# Deneigus_PI_Arduino.net
KiCad netlist of a schematic drawn in Altium Designer
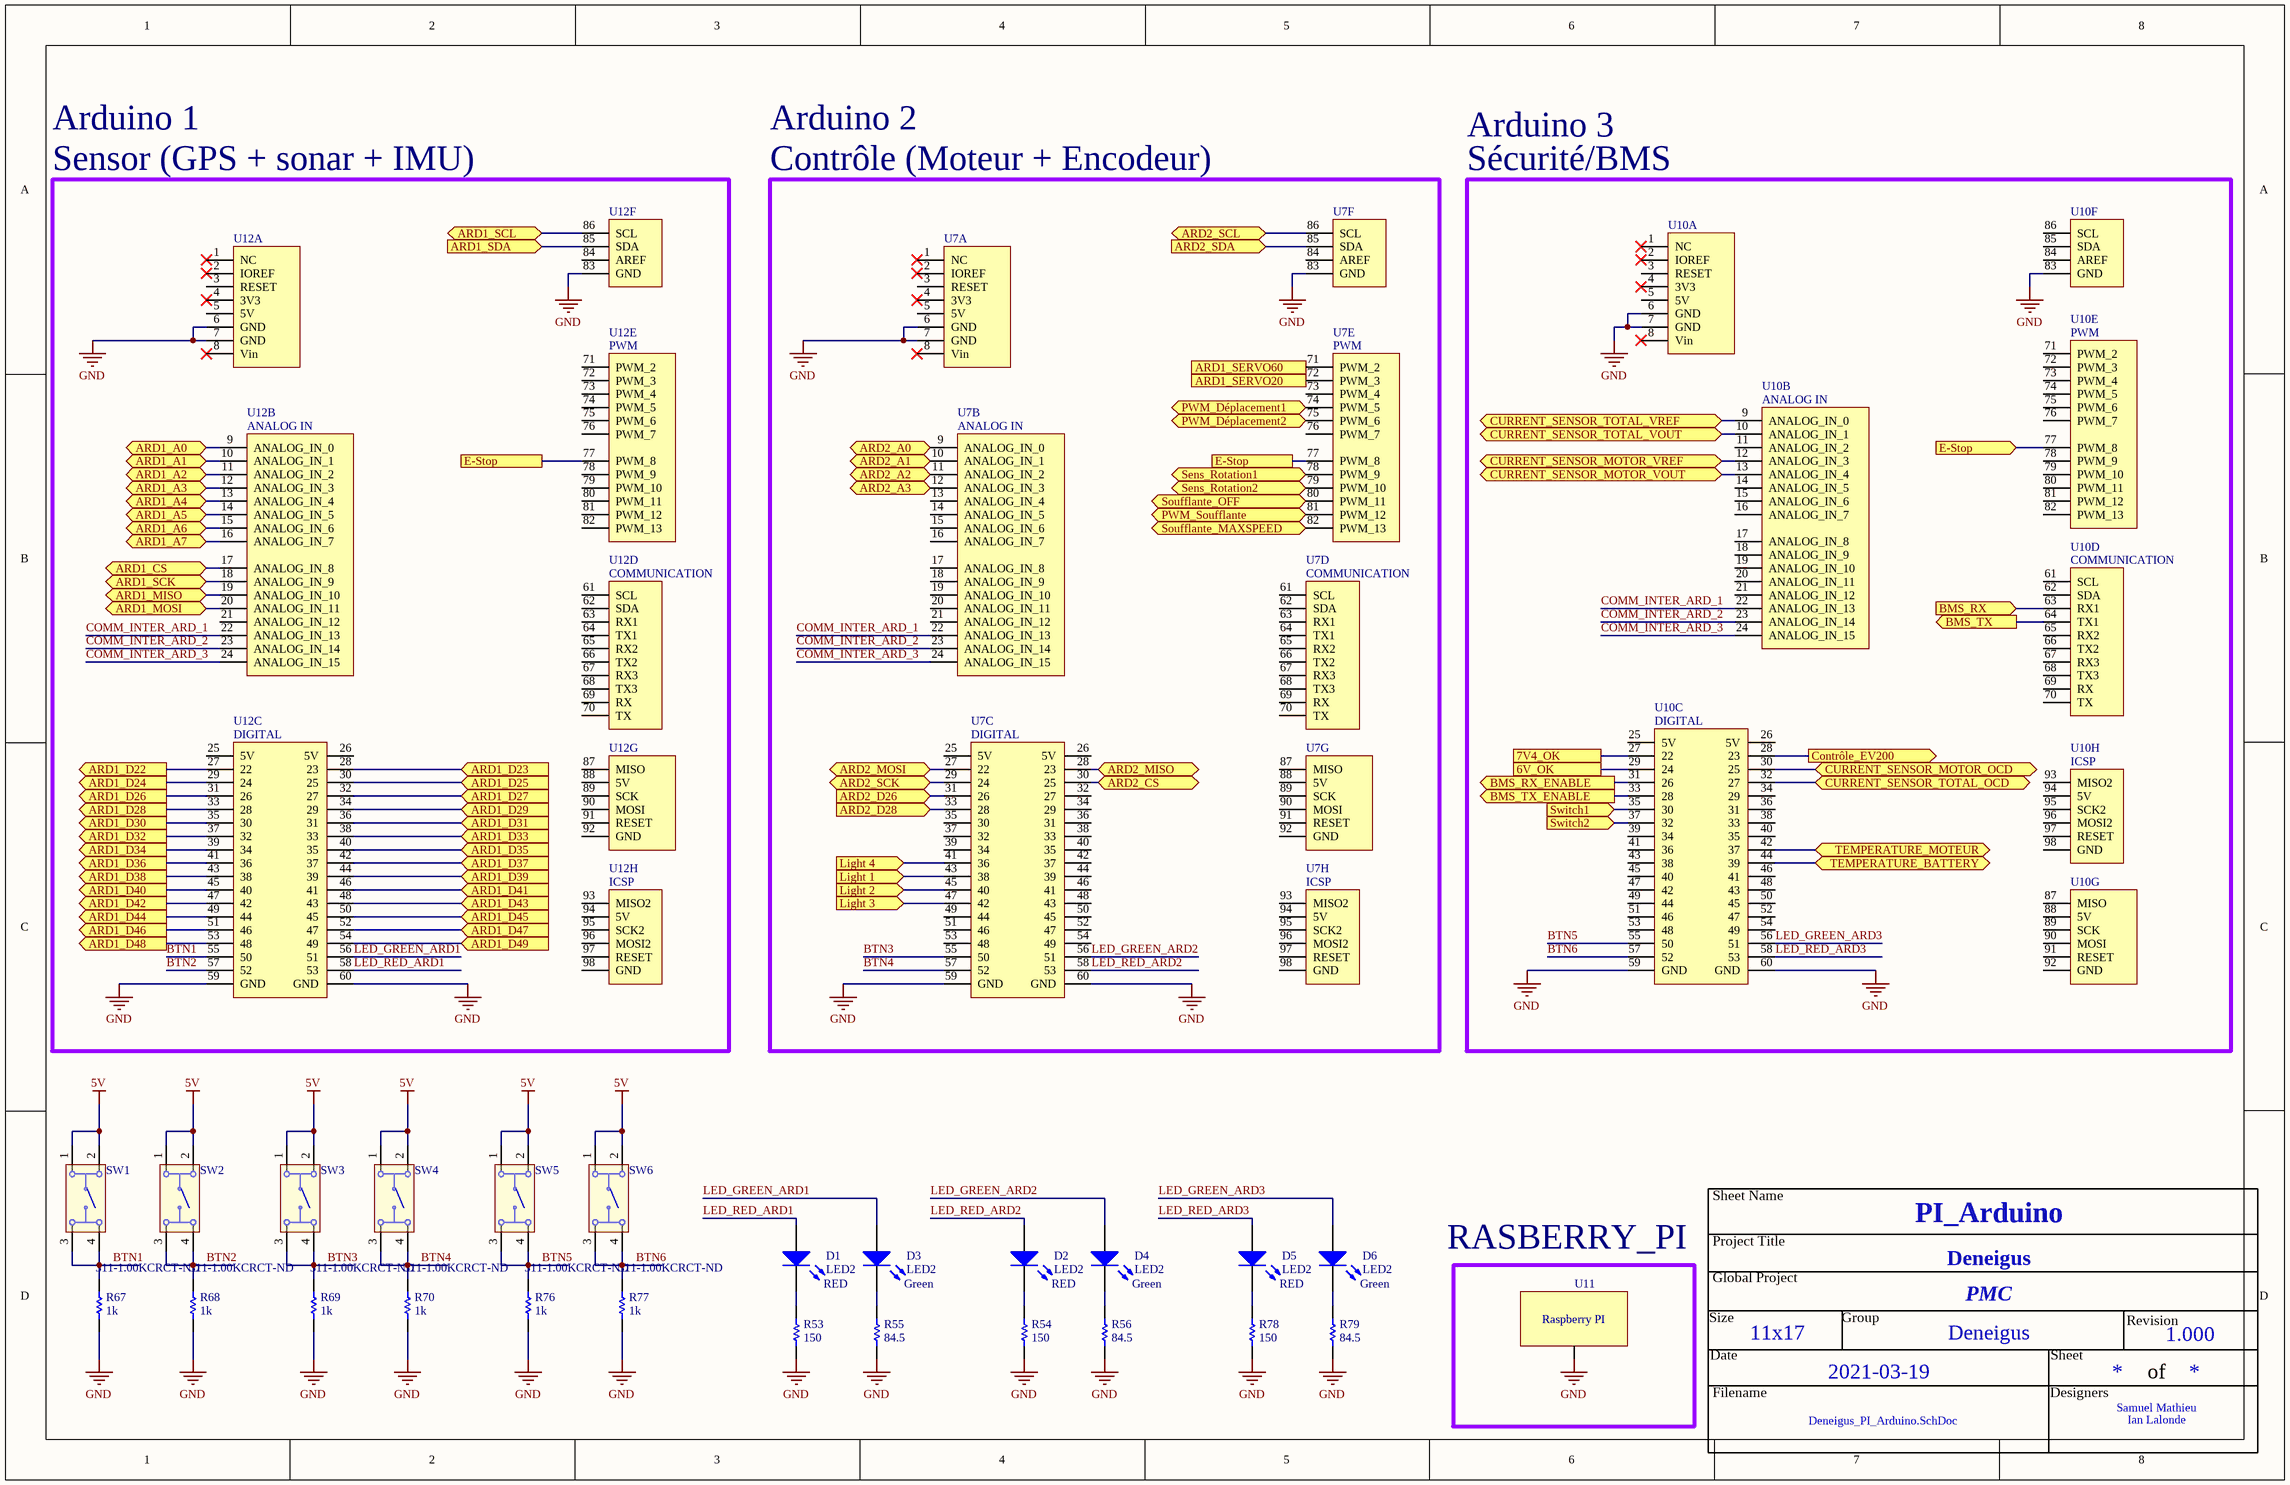
[diagram p0: Deneigus_PI_Arduino.SchDoc]

(export (version "E")
  (design (tool "Eeschema 10.0.6"))
  (components
    (comp (ref "D1")
      (value "LED2")
      (footprint "S7CAS-APP1:DEL")
      (description "Typical RED, GREEN, YELLOW, AMBER GaAs LED")
      (fields (field (name "COLOR") "RED") (field (name "PUBLISHER") "Altium Limited"))
      (libsource (lib "Miscellaneous Devices") (part "LED2"))
    )
    (comp (ref "D2")
      (value "LED2")
      (footprint "S7CAS-APP1:DEL")
      (description "Typical RED, GREEN, YELLOW, AMBER GaAs LED")
      (fields (field (name "COLOR") "RED") (field (name "PUBLISHER") "Altium Limited"))
      (libsource (lib "Miscellaneous Devices") (part "LED2"))
    )
    (comp (ref "D3")
      (value "LED2")
      (footprint "S7CAS-APP1:DEL")
      (description "Typical RED, GREEN, YELLOW, AMBER GaAs LED")
      (fields (field (name "COLOR") "Green") (field (name "PUBLISHER") "Altium Limited"))
      (libsource (lib "Miscellaneous Devices") (part "LED2"))
    )
    (comp (ref "D4")
      (value "LED2")
      (footprint "S7CAS-APP1:DEL")
      (description "Typical RED, GREEN, YELLOW, AMBER GaAs LED")
      (fields (field (name "COLOR") "Green") (field (name "PUBLISHER") "Altium Limited"))
      (libsource (lib "Miscellaneous Devices") (part "LED2"))
    )
    (comp (ref "D5")
      (value "LED2")
      (footprint "S7CAS-APP1:DEL")
      (description "Typical RED, GREEN, YELLOW, AMBER GaAs LED")
      (fields (field (name "COLOR") "RED") (field (name "PUBLISHER") "Altium Limited"))
      (libsource (lib "Miscellaneous Devices") (part "LED2"))
    )
    (comp (ref "D6")
      (value "LED2")
      (footprint "S7CAS-APP1:DEL")
      (description "Typical RED, GREEN, YELLOW, AMBER GaAs LED")
      (fields (field (name "COLOR") "Green") (field (name "PUBLISHER") "Altium Limited"))
      (libsource (lib "Miscellaneous Devices") (part "LED2"))
    )
    (comp (ref "R53")
      (value "150")
      (footprint "RES_0805")
      (description "Resistor")
      (fields (field (name "Comment") "Res1") (field (name "PUBLISHER") "Altium Limited"))
      (libsource (lib "Miscellaneous Devices") (part "Res1"))
    )
    (comp (ref "R54")
      (value "150")
      (footprint "RES_0805")
      (description "Resistor")
      (fields (field (name "Comment") "Res1") (field (name "PUBLISHER") "Altium Limited"))
      (libsource (lib "Miscellaneous Devices") (part "Res1"))
    )
    (comp (ref "R55")
      (value "84.5")
      (footprint "RES_0805")
      (description "Resistor")
      (fields (field (name "Comment") "Res1") (field (name "PUBLISHER") "Altium Limited"))
      (libsource (lib "Miscellaneous Devices") (part "Res1"))
    )
    (comp (ref "R56")
      (value "84.5")
      (footprint "RES_0805")
      (description "Resistor")
      (fields (field (name "Comment") "Res1") (field (name "PUBLISHER") "Altium Limited"))
      (libsource (lib "Miscellaneous Devices") (part "Res1"))
    )
    (comp (ref "R67")
      (value "1k")
      (footprint "RES_0805")
      (description "Resistor")
      (fields
        (field (name "SUPPLIER PART NUMBER 1") "311-1.00KCRCT-ND")
        (field (name "Comment") "Res1")
        (field (name "PUBLISHER") "Altium Limited")
      )
      (libsource (lib "Miscellaneous Devices") (part "Res1"))
    )
    (comp (ref "R68")
      (value "1k")
      (footprint "RES_0805")
      (description "Resistor")
      (fields
        (field (name "SUPPLIER PART NUMBER 1") "311-1.00KCRCT-ND")
        (field (name "Comment") "Res1")
        (field (name "PUBLISHER") "Altium Limited")
      )
      (libsource (lib "Miscellaneous Devices") (part "Res1"))
    )
    (comp (ref "R69")
      (value "1k")
      (footprint "RES_0805")
      (description "Resistor")
      (fields
        (field (name "SUPPLIER PART NUMBER 1") "311-1.00KCRCT-ND")
        (field (name "Comment") "Res1")
        (field (name "PUBLISHER") "Altium Limited")
      )
      (libsource (lib "Miscellaneous Devices") (part "Res1"))
    )
    (comp (ref "R70")
      (value "1k")
      (footprint "RES_0805")
      (description "Resistor")
      (fields
        (field (name "SUPPLIER PART NUMBER 1") "311-1.00KCRCT-ND")
        (field (name "Comment") "Res1")
        (field (name "PUBLISHER") "Altium Limited")
      )
      (libsource (lib "Miscellaneous Devices") (part "Res1"))
    )
    (comp (ref "R76")
      (value "1k")
      (footprint "RES_0805")
      (description "Resistor")
      (fields
        (field (name "SUPPLIER PART NUMBER 1") "311-1.00KCRCT-ND")
        (field (name "Comment") "Res1")
        (field (name "PUBLISHER") "Altium Limited")
      )
      (libsource (lib "Miscellaneous Devices") (part "Res1"))
    )
    (comp (ref "R77")
      (value "1k")
      (footprint "RES_0805")
      (description "Resistor")
      (fields
        (field (name "SUPPLIER PART NUMBER 1") "311-1.00KCRCT-ND")
        (field (name "Comment") "Res1")
        (field (name "PUBLISHER") "Altium Limited")
      )
      (libsource (lib "Miscellaneous Devices") (part "Res1"))
    )
    (comp (ref "R78")
      (value "150")
      (footprint "RES_0805")
      (description "Resistor")
      (fields (field (name "Comment") "Res1") (field (name "PUBLISHER") "Altium Limited"))
      (libsource (lib "Miscellaneous Devices") (part "Res1"))
    )
    (comp (ref "R79")
      (value "84.5")
      (footprint "RES_0805")
      (description "Resistor")
      (fields (field (name "Comment") "Res1") (field (name "PUBLISHER") "Altium Limited"))
      (libsource (lib "Miscellaneous Devices") (part "Res1"))
    )
    (comp (ref "SW1")
      (value "430181038816")
      (footprint "430181038816")
      (description "WS-TASV SMD Tact Switch 4.5X4.5 mm")
      (fields (field (name "MANUFACTURER") "Wuerth Elektronik"))
      (libsource (lib "Altium Content Vault") (part "WE-TACT-SW-4_A"))
    )
    (comp (ref "SW2")
      (value "430181038816")
      (footprint "430181038816")
      (description "WS-TASV SMD Tact Switch 4.5X4.5 mm")
      (fields (field (name "MANUFACTURER") "Wuerth Elektronik"))
      (libsource (lib "Altium Content Vault") (part "WE-TACT-SW-4_A"))
    )
    (comp (ref "SW3")
      (value "430181038816")
      (footprint "430181038816")
      (description "WS-TASV SMD Tact Switch 4.5X4.5 mm")
      (fields (field (name "MANUFACTURER") "Wuerth Elektronik"))
      (libsource (lib "Altium Content Vault") (part "WE-TACT-SW-4_A"))
    )
    (comp (ref "SW4")
      (value "430181038816")
      (footprint "430181038816")
      (description "WS-TASV SMD Tact Switch 4.5X4.5 mm")
      (fields (field (name "MANUFACTURER") "Wuerth Elektronik"))
      (libsource (lib "Altium Content Vault") (part "WE-TACT-SW-4_A"))
    )
    (comp (ref "SW5")
      (value "430181038816")
      (footprint "430181038816")
      (description "WS-TASV SMD Tact Switch 4.5X4.5 mm")
      (fields (field (name "MANUFACTURER") "Wuerth Elektronik"))
      (libsource (lib "Altium Content Vault") (part "WE-TACT-SW-4_A"))
    )
    (comp (ref "SW6")
      (value "430181038816")
      (footprint "430181038816")
      (description "WS-TASV SMD Tact Switch 4.5X4.5 mm")
      (fields (field (name "MANUFACTURER") "Wuerth Elektronik"))
      (libsource (lib "Altium Content Vault") (part "WE-TACT-SW-4_A"))
    )
    (comp (ref "U7")
      (value "Arduino_Mega")
      (footprint "Arduino_Mega")
      (libsource (lib "S7CAS-APP1") (part "Arduino_Mega"))
    )
    (comp (ref "U10")
      (value "Arduino_Mega")
      (footprint "Arduino_Mega")
      (libsource (lib "S7CAS-APP1") (part "Arduino_Mega"))
    )
    (comp (ref "U11")
      (value "Raspberry PI 4")
      (footprint "Raspberry Pi 4")
      (libsource (lib "S7CAS-APP1") (part "Raspberry PI 4"))
    )
    (comp (ref "U12")
      (value "Arduino_Mega")
      (footprint "Arduino_Mega")
      (libsource (lib "S7CAS-APP1") (part "Arduino_Mega"))
    )
  )
  (nets
    (net (code "1") (name "/6V_OK") (class "Default")
      (node (ref "U10") (pin "29") (pinfunction "24_29") (pintype "passive"))
    )
    (net (code "2") (name "/7V4_OK") (class "Default")
      (node (ref "U10") (pin "27") (pinfunction "22_27") (pintype "passive"))
    )
    (net (code "3") (name "/ARD1_A0") (class "Default")
      (node (ref "U12") (pin "9") (pinfunction "ANALOG_IN_0_9") (pintype "passive"))
    )
    (net (code "4") (name "/ARD1_A1") (class "Default")
      (node (ref "U12") (pin "10") (pinfunction "ANALOG_IN_1_10") (pintype "passive"))
    )
    (net (code "5") (name "/ARD1_A2") (class "Default")
      (node (ref "U12") (pin "11") (pinfunction "ANALOG_IN_2_11") (pintype "passive"))
    )
    (net (code "6") (name "/ARD1_A3") (class "Default")
      (node (ref "U12") (pin "12") (pinfunction "ANALOG_IN_3_12") (pintype "passive"))
    )
    (net (code "7") (name "/ARD1_A4") (class "Default")
      (node (ref "U12") (pin "13") (pinfunction "ANALOG_IN_4_13") (pintype "passive"))
    )
    (net (code "8") (name "/ARD1_A5") (class "Default")
      (node (ref "U12") (pin "14") (pinfunction "ANALOG_IN_5_14") (pintype "passive"))
    )
    (net (code "9") (name "/ARD1_A6") (class "Default")
      (node (ref "U12") (pin "15") (pinfunction "ANALOG_IN_6_15") (pintype "passive"))
    )
    (net (code "10") (name "/ARD1_A7") (class "Default")
      (node (ref "U12") (pin "16") (pinfunction "ANALOG_IN_7_16") (pintype "passive"))
    )
    (net (code "11") (name "/ARD1_CS") (class "Default")
      (node (ref "U12") (pin "17") (pinfunction "ANALOG_IN_8_17") (pintype "passive"))
    )
    (net (code "12") (name "/ARD1_D22") (class "Default")
      (node (ref "U12") (pin "27") (pinfunction "22_27") (pintype "passive"))
    )
    (net (code "13") (name "/ARD1_D23") (class "Default")
      (node (ref "U12") (pin "28") (pinfunction "23_28") (pintype "passive"))
    )
    (net (code "14") (name "/ARD1_D24") (class "Default")
      (node (ref "U12") (pin "29") (pinfunction "24_29") (pintype "passive"))
    )
    (net (code "15") (name "/ARD1_D25") (class "Default")
      (node (ref "U12") (pin "30") (pinfunction "25_30") (pintype "passive"))
    )
    (net (code "16") (name "/ARD1_D26") (class "Default")
      (node (ref "U12") (pin "31") (pinfunction "26_31") (pintype "passive"))
    )
    (net (code "17") (name "/ARD1_D27") (class "Default")
      (node (ref "U12") (pin "32") (pinfunction "27_32") (pintype "passive"))
    )
    (net (code "18") (name "/ARD1_D28") (class "Default")
      (node (ref "U12") (pin "33") (pinfunction "28_33") (pintype "passive"))
    )
    (net (code "19") (name "/ARD1_D29") (class "Default")
      (node (ref "U12") (pin "34") (pinfunction "29_34") (pintype "passive"))
    )
    (net (code "20") (name "/ARD1_D30") (class "Default")
      (node (ref "U12") (pin "35") (pinfunction "30_35") (pintype "passive"))
    )
    (net (code "21") (name "/ARD1_D31") (class "Default")
      (node (ref "U12") (pin "36") (pinfunction "31_36") (pintype "passive"))
    )
    (net (code "22") (name "/ARD1_D32") (class "Default")
      (node (ref "U12") (pin "37") (pinfunction "32_37") (pintype "passive"))
    )
    (net (code "23") (name "/ARD1_D33") (class "Default")
      (node (ref "U12") (pin "38") (pinfunction "33_38") (pintype "passive"))
    )
    (net (code "24") (name "/ARD1_D34") (class "Default")
      (node (ref "U12") (pin "39") (pinfunction "34_39") (pintype "passive"))
    )
    (net (code "25") (name "/ARD1_D35") (class "Default")
      (node (ref "U12") (pin "40") (pinfunction "35_40") (pintype "passive"))
    )
    (net (code "26") (name "/ARD1_D36") (class "Default")
      (node (ref "U12") (pin "41") (pinfunction "36_41") (pintype "passive"))
    )
    (net (code "27") (name "/ARD1_D37") (class "Default")
      (node (ref "U12") (pin "42") (pinfunction "37_42") (pintype "passive"))
    )
    (net (code "28") (name "/ARD1_D38") (class "Default")
      (node (ref "U12") (pin "43") (pinfunction "38_43") (pintype "passive"))
    )
    (net (code "29") (name "/ARD1_D39") (class "Default")
      (node (ref "U12") (pin "44") (pinfunction "39_44") (pintype "passive"))
    )
    (net (code "30") (name "/ARD1_D40") (class "Default")
      (node (ref "U12") (pin "45") (pinfunction "40_45") (pintype "passive"))
    )
    (net (code "31") (name "/ARD1_D41") (class "Default")
      (node (ref "U12") (pin "46") (pinfunction "41_46") (pintype "passive"))
    )
    (net (code "32") (name "/ARD1_D42") (class "Default")
      (node (ref "U12") (pin "47") (pinfunction "42_47") (pintype "passive"))
    )
    (net (code "33") (name "/ARD1_D43") (class "Default")
      (node (ref "U12") (pin "48") (pinfunction "43_48") (pintype "passive"))
    )
    (net (code "34") (name "/ARD1_D44") (class "Default")
      (node (ref "U12") (pin "49") (pinfunction "44_49") (pintype "passive"))
    )
    (net (code "35") (name "/ARD1_D45") (class "Default")
      (node (ref "U12") (pin "50") (pinfunction "45_50") (pintype "passive"))
    )
    (net (code "36") (name "/ARD1_D46") (class "Default")
      (node (ref "U12") (pin "51") (pinfunction "46_51") (pintype "passive"))
    )
    (net (code "37") (name "/ARD1_D47") (class "Default")
      (node (ref "U12") (pin "52") (pinfunction "47_52") (pintype "passive"))
    )
    (net (code "38") (name "/ARD1_D48") (class "Default")
      (node (ref "U12") (pin "53") (pinfunction "48_53") (pintype "passive"))
    )
    (net (code "39") (name "/ARD1_D49") (class "Default")
      (node (ref "U12") (pin "54") (pinfunction "49_54") (pintype "passive"))
    )
    (net (code "40") (name "/ARD1_MISO") (class "Default")
      (node (ref "U12") (pin "19") (pinfunction "ANALOG_IN_10_19") (pintype "passive"))
    )
    (net (code "41") (name "/ARD1_MOSI") (class "Default")
      (node (ref "U12") (pin "20") (pinfunction "ANALOG_IN_11_20") (pintype "passive"))
    )
    (net (code "42") (name "/ARD1_SCK") (class "Default")
      (node (ref "U12") (pin "18") (pinfunction "ANALOG_IN_9_18") (pintype "passive"))
    )
    (net (code "43") (name "/ARD1_SCL") (class "Default")
      (node (ref "U12") (pin "86") (pinfunction "SCL_86") (pintype "passive"))
    )
    (net (code "44") (name "/ARD1_SDA") (class "Default")
      (node (ref "U12") (pin "85") (pinfunction "SDA_85") (pintype "passive"))
    )
    (net (code "45") (name "/ARD1_SERVO20") (class "Default")
      (node (ref "U7") (pin "72") (pinfunction "PWM_3_72") (pintype "passive"))
    )
    (net (code "46") (name "/ARD1_SERVO60") (class "Default")
      (node (ref "U7") (pin "71") (pinfunction "PWM_2_71") (pintype "passive"))
    )
    (net (code "47") (name "/ARD2_A0") (class "Default")
      (node (ref "U7") (pin "9") (pinfunction "ANALOG_IN_0_9") (pintype "passive"))
    )
    (net (code "48") (name "/ARD2_A1") (class "Default")
      (node (ref "U7") (pin "10") (pinfunction "ANALOG_IN_1_10") (pintype "passive"))
    )
    (net (code "49") (name "/ARD2_A2") (class "Default")
      (node (ref "U7") (pin "11") (pinfunction "ANALOG_IN_2_11") (pintype "passive"))
    )
    (net (code "50") (name "/ARD2_A3") (class "Default")
      (node (ref "U7") (pin "12") (pinfunction "ANALOG_IN_3_12") (pintype "passive"))
    )
    (net (code "51") (name "/ARD2_CS") (class "Default")
      (node (ref "U7") (pin "30") (pinfunction "25_30") (pintype "passive"))
    )
    (net (code "52") (name "/ARD2_D26") (class "Default")
      (node (ref "U7") (pin "31") (pinfunction "26_31") (pintype "passive"))
    )
    (net (code "53") (name "/ARD2_D28") (class "Default")
      (node (ref "U7") (pin "33") (pinfunction "28_33") (pintype "passive"))
    )
    (net (code "54") (name "/ARD2_MISO") (class "Default")
      (node (ref "U7") (pin "28") (pinfunction "23_28") (pintype "passive"))
    )
    (net (code "55") (name "/ARD2_MOSI") (class "Default")
      (node (ref "U7") (pin "27") (pinfunction "22_27") (pintype "passive"))
    )
    (net (code "56") (name "/ARD2_SCK") (class "Default")
      (node (ref "U7") (pin "29") (pinfunction "24_29") (pintype "passive"))
    )
    (net (code "57") (name "/ARD2_SCL") (class "Default")
      (node (ref "U7") (pin "86") (pinfunction "SCL_86") (pintype "passive"))
    )
    (net (code "58") (name "/ARD2_SDA") (class "Default")
      (node (ref "U7") (pin "85") (pinfunction "SDA_85") (pintype "passive"))
    )
    (net (code "59") (name "/BMS_RX") (class "Default")
      (node (ref "U10") (pin "63") (pinfunction "RX1_63") (pintype "passive"))
    )
    (net (code "60") (name "/BMS_RX_ENABLE") (class "Default")
      (node (ref "U10") (pin "31") (pinfunction "26_31") (pintype "passive"))
    )
    (net (code "61") (name "/BMS_TX") (class "Default")
      (node (ref "U10") (pin "64") (pinfunction "TX1_64") (pintype "passive"))
    )
    (net (code "62") (name "/BMS_TX_ENABLE") (class "Default")
      (node (ref "U10") (pin "33") (pinfunction "28_33") (pintype "passive"))
    )
    (net (code "63") (name "/BTN1") (class "Default")
      (node (ref "R67") (pin "1") (pinfunction "1_1") (pintype "passive"))
      (node (ref "SW1") (pin "3") (pinfunction "3_3") (pintype "passive"))
      (node (ref "SW1") (pin "4") (pinfunction "4_4") (pintype "passive"))
      (node (ref "U12") (pin "55") (pinfunction "50_55") (pintype "passive"))
    )
    (net (code "64") (name "/BTN2") (class "Default")
      (node (ref "R68") (pin "1") (pinfunction "1_1") (pintype "passive"))
      (node (ref "SW2") (pin "3") (pinfunction "3_3") (pintype "passive"))
      (node (ref "SW2") (pin "4") (pinfunction "4_4") (pintype "passive"))
      (node (ref "U12") (pin "57") (pinfunction "52_57") (pintype "passive"))
    )
    (net (code "65") (name "/BTN3") (class "Default")
      (node (ref "R69") (pin "1") (pinfunction "1_1") (pintype "passive"))
      (node (ref "SW3") (pin "3") (pinfunction "3_3") (pintype "passive"))
      (node (ref "SW3") (pin "4") (pinfunction "4_4") (pintype "passive"))
      (node (ref "U7") (pin "55") (pinfunction "50_55") (pintype "passive"))
    )
    (net (code "66") (name "/BTN4") (class "Default")
      (node (ref "R70") (pin "1") (pinfunction "1_1") (pintype "passive"))
      (node (ref "SW4") (pin "3") (pinfunction "3_3") (pintype "passive"))
      (node (ref "SW4") (pin "4") (pinfunction "4_4") (pintype "passive"))
      (node (ref "U7") (pin "57") (pinfunction "52_57") (pintype "passive"))
    )
    (net (code "67") (name "/BTN5") (class "Default")
      (node (ref "R76") (pin "1") (pinfunction "1_1") (pintype "passive"))
      (node (ref "SW5") (pin "3") (pinfunction "3_3") (pintype "passive"))
      (node (ref "SW5") (pin "4") (pinfunction "4_4") (pintype "passive"))
      (node (ref "U10") (pin "55") (pinfunction "50_55") (pintype "passive"))
    )
    (net (code "68") (name "/BTN6") (class "Default")
      (node (ref "R77") (pin "1") (pinfunction "1_1") (pintype "passive"))
      (node (ref "SW6") (pin "3") (pinfunction "3_3") (pintype "passive"))
      (node (ref "SW6") (pin "4") (pinfunction "4_4") (pintype "passive"))
      (node (ref "U10") (pin "57") (pinfunction "52_57") (pintype "passive"))
    )
    (net (code "69") (name "/COMM_INTER_ARD_1") (class "Default")
      (node (ref "U10") (pin "22") (pinfunction "ANALOG_IN_13_22") (pintype "passive"))
      (node (ref "U12") (pin "22") (pinfunction "ANALOG_IN_13_22") (pintype "passive"))
      (node (ref "U7") (pin "22") (pinfunction "ANALOG_IN_13_22") (pintype "passive"))
    )
    (net (code "70") (name "/COMM_INTER_ARD_2") (class "Default")
      (node (ref "U10") (pin "23") (pinfunction "ANALOG_IN_14_23") (pintype "passive"))
      (node (ref "U12") (pin "23") (pinfunction "ANALOG_IN_14_23") (pintype "passive"))
      (node (ref "U7") (pin "23") (pinfunction "ANALOG_IN_14_23") (pintype "passive"))
    )
    (net (code "71") (name "/COMM_INTER_ARD_3") (class "Default")
      (node (ref "U10") (pin "24") (pinfunction "ANALOG_IN_15_24") (pintype "passive"))
      (node (ref "U12") (pin "24") (pinfunction "ANALOG_IN_15_24") (pintype "passive"))
      (node (ref "U7") (pin "24") (pinfunction "ANALOG_IN_15_24") (pintype "passive"))
    )
    (net (code "72") (name "/CURRENT_SENSOR_MOTOR_OCD") (class "Default")
      (node (ref "U10") (pin "30") (pinfunction "25_30") (pintype "passive"))
    )
    (net (code "73") (name "/CURRENT_SENSOR_MOTOR_VOUT") (class "Default")
      (node (ref "U10") (pin "13") (pinfunction "ANALOG_IN_4_13") (pintype "passive"))
    )
    (net (code "74") (name "/CURRENT_SENSOR_MOTOR_VREF") (class "Default")
      (node (ref "U10") (pin "12") (pinfunction "ANALOG_IN_3_12") (pintype "passive"))
    )
    (net (code "75") (name "/CURRENT_SENSOR_TOTAL_OCD") (class "Default")
      (node (ref "U10") (pin "32") (pinfunction "27_32") (pintype "passive"))
    )
    (net (code "76") (name "/CURRENT_SENSOR_TOTAL_VOUT") (class "Default")
      (node (ref "U10") (pin "10") (pinfunction "ANALOG_IN_1_10") (pintype "passive"))
    )
    (net (code "77") (name "/CURRENT_SENSOR_TOTAL_VREF") (class "Default")
      (node (ref "U10") (pin "9") (pinfunction "ANALOG_IN_0_9") (pintype "passive"))
    )
    (net (code "78") (name "/Contrôle_EV200") (class "Default")
      (node (ref "U10") (pin "28") (pinfunction "23_28") (pintype "passive"))
    )
    (net (code "79") (name "/E-Stop") (class "Default")
      (node (ref "U10") (pin "77") (pinfunction "PWM_8_77") (pintype "passive"))
      (node (ref "U12") (pin "77") (pinfunction "PWM_8_77") (pintype "passive"))
      (node (ref "U7") (pin "77") (pinfunction "PWM_8_77") (pintype "passive"))
    )
    (net (code "80") (name "/LED_GREEN_ARD1") (class "Default")
      (node (ref "D3") (pin "1") (pinfunction "A_1") (pintype "passive"))
      (node (ref "U12") (pin "56") (pinfunction "51_56") (pintype "passive"))
    )
    (net (code "81") (name "/LED_GREEN_ARD2") (class "Default")
      (node (ref "D4") (pin "1") (pinfunction "A_1") (pintype "passive"))
      (node (ref "U7") (pin "56") (pinfunction "51_56") (pintype "passive"))
    )
    (net (code "82") (name "/LED_GREEN_ARD3") (class "Default")
      (node (ref "D6") (pin "1") (pinfunction "A_1") (pintype "passive"))
      (node (ref "U10") (pin "56") (pinfunction "51_56") (pintype "passive"))
    )
    (net (code "83") (name "/LED_RED_ARD1") (class "Default")
      (node (ref "D1") (pin "1") (pinfunction "A_1") (pintype "passive"))
      (node (ref "U12") (pin "58") (pinfunction "53_58") (pintype "passive"))
    )
    (net (code "84") (name "/LED_RED_ARD2") (class "Default")
      (node (ref "D2") (pin "1") (pinfunction "A_1") (pintype "passive"))
      (node (ref "U7") (pin "58") (pinfunction "53_58") (pintype "passive"))
    )
    (net (code "85") (name "/LED_RED_ARD3") (class "Default")
      (node (ref "D5") (pin "1") (pinfunction "A_1") (pintype "passive"))
      (node (ref "U10") (pin "58") (pinfunction "53_58") (pintype "passive"))
    )
    (net (code "86") (name "/Light 1") (class "Default")
      (node (ref "U7") (pin "43") (pinfunction "38_43") (pintype "passive"))
    )
    (net (code "87") (name "/Light 2") (class "Default")
      (node (ref "U7") (pin "45") (pinfunction "40_45") (pintype "passive"))
    )
    (net (code "88") (name "/Light 3") (class "Default")
      (node (ref "U7") (pin "47") (pinfunction "42_47") (pintype "passive"))
    )
    (net (code "89") (name "/Light 4") (class "Default")
      (node (ref "U7") (pin "41") (pinfunction "36_41") (pintype "passive"))
    )
    (net (code "90") (name "/PWM_Déplacement1") (class "Default")
      (node (ref "U7") (pin "74") (pinfunction "PWM_5_74") (pintype "passive"))
    )
    (net (code "91") (name "/PWM_Déplacement2") (class "Default")
      (node (ref "U7") (pin "75") (pinfunction "PWM_6_75") (pintype "passive"))
    )
    (net (code "92") (name "/PWM_Soufflante") (class "Default")
      (node (ref "U7") (pin "81") (pinfunction "PWM_12_81") (pintype "passive"))
    )
    (net (code "93") (name "/Sens_Rotation1") (class "Default")
      (node (ref "U7") (pin "78") (pinfunction "PWM_9_78") (pintype "passive"))
    )
    (net (code "94") (name "/Sens_Rotation2") (class "Default")
      (node (ref "U7") (pin "79") (pinfunction "PWM_10_79") (pintype "passive"))
    )
    (net (code "95") (name "/Soufflante_MAXSPEED") (class "Default")
      (node (ref "U7") (pin "82") (pinfunction "PWM_13_82") (pintype "passive"))
    )
    (net (code "96") (name "/Soufflante_OFF") (class "Default")
      (node (ref "U7") (pin "80") (pinfunction "PWM_11_80") (pintype "passive"))
    )
    (net (code "97") (name "/Switch1") (class "Default")
      (node (ref "U10") (pin "35") (pinfunction "30_35") (pintype "passive"))
    )
    (net (code "98") (name "/Switch2") (class "Default")
      (node (ref "U10") (pin "37") (pinfunction "32_37") (pintype "passive"))
    )
    (net (code "99") (name "/TEMPERATURE_BATTERY") (class "Default")
      (node (ref "U10") (pin "44") (pinfunction "39_44") (pintype "passive"))
    )
    (net (code "100") (name "/TEMPERATURE_MOTEUR") (class "Default")
      (node (ref "U10") (pin "42") (pinfunction "37_42") (pintype "passive"))
    )
    (net (code "101") (name "5V") (class "Default")
      (node (ref "SW1") (pin "1") (pinfunction "1_1") (pintype "passive"))
      (node (ref "SW1") (pin "2") (pinfunction "2_2") (pintype "passive"))
      (node (ref "SW2") (pin "1") (pinfunction "1_1") (pintype "passive"))
      (node (ref "SW2") (pin "2") (pinfunction "2_2") (pintype "passive"))
      (node (ref "SW3") (pin "1") (pinfunction "1_1") (pintype "passive"))
      (node (ref "SW3") (pin "2") (pinfunction "2_2") (pintype "passive"))
      (node (ref "SW4") (pin "1") (pinfunction "1_1") (pintype "passive"))
      (node (ref "SW4") (pin "2") (pinfunction "2_2") (pintype "passive"))
      (node (ref "SW5") (pin "1") (pinfunction "1_1") (pintype "passive"))
      (node (ref "SW5") (pin "2") (pinfunction "2_2") (pintype "passive"))
      (node (ref "SW6") (pin "1") (pinfunction "1_1") (pintype "passive"))
      (node (ref "SW6") (pin "2") (pinfunction "2_2") (pintype "passive"))
    )
    (net (code "102") (name "GND") (class "Default")
      (node (ref "R53") (pin "2") (pinfunction "2_2") (pintype "passive"))
      (node (ref "R54") (pin "2") (pinfunction "2_2") (pintype "passive"))
      (node (ref "R55") (pin "2") (pinfunction "2_2") (pintype "passive"))
      (node (ref "R56") (pin "2") (pinfunction "2_2") (pintype "passive"))
      (node (ref "R67") (pin "2") (pinfunction "2_2") (pintype "passive"))
      (node (ref "R68") (pin "2") (pinfunction "2_2") (pintype "passive"))
      (node (ref "R69") (pin "2") (pinfunction "2_2") (pintype "passive"))
      (node (ref "R70") (pin "2") (pinfunction "2_2") (pintype "passive"))
      (node (ref "R76") (pin "2") (pinfunction "2_2") (pintype "passive"))
      (node (ref "R77") (pin "2") (pinfunction "2_2") (pintype "passive"))
      (node (ref "R78") (pin "2") (pinfunction "2_2") (pintype "passive"))
      (node (ref "R79") (pin "2") (pinfunction "2_2") (pintype "passive"))
      (node (ref "U10") (pin "59") (pinfunction "GND_59") (pintype "passive"))
      (node (ref "U10") (pin "6") (pinfunction "GND_6") (pintype "passive"))
      (node (ref "U10") (pin "60") (pinfunction "GND_60") (pintype "passive"))
      (node (ref "U10") (pin "7") (pinfunction "GND_7") (pintype "passive"))
      (node (ref "U10") (pin "83") (pinfunction "GND_83") (pintype "passive"))
      (node (ref "U11") (pin "0") (pinfunction "0_0") (pintype "passive"))
      (node (ref "U12") (pin "59") (pinfunction "GND_59") (pintype "passive"))
      (node (ref "U12") (pin "6") (pinfunction "GND_6") (pintype "passive"))
      (node (ref "U12") (pin "60") (pinfunction "GND_60") (pintype "passive"))
      (node (ref "U12") (pin "7") (pinfunction "GND_7") (pintype "passive"))
      (node (ref "U12") (pin "83") (pinfunction "GND_83") (pintype "passive"))
      (node (ref "U7") (pin "59") (pinfunction "GND_59") (pintype "passive"))
      (node (ref "U7") (pin "6") (pinfunction "GND_6") (pintype "passive"))
      (node (ref "U7") (pin "60") (pinfunction "GND_60") (pintype "passive"))
      (node (ref "U7") (pin "7") (pinfunction "GND_7") (pintype "passive"))
      (node (ref "U7") (pin "83") (pinfunction "GND_83") (pintype "passive"))
    )
    (net (code "103") (name "Net-(D1-K)") (class "Default")
      (node (ref "D1") (pin "2") (pinfunction "K_2") (pintype "passive"))
      (node (ref "R53") (pin "1") (pinfunction "1_1") (pintype "passive"))
    )
    (net (code "104") (name "Net-(D2-K)") (class "Default")
      (node (ref "D2") (pin "2") (pinfunction "K_2") (pintype "passive"))
      (node (ref "R54") (pin "1") (pinfunction "1_1") (pintype "passive"))
    )
    (net (code "105") (name "Net-(D3-K)") (class "Default")
      (node (ref "D3") (pin "2") (pinfunction "K_2") (pintype "passive"))
      (node (ref "R55") (pin "1") (pinfunction "1_1") (pintype "passive"))
    )
    (net (code "106") (name "Net-(D4-K)") (class "Default")
      (node (ref "D4") (pin "2") (pinfunction "K_2") (pintype "passive"))
      (node (ref "R56") (pin "1") (pinfunction "1_1") (pintype "passive"))
    )
    (net (code "107") (name "Net-(D5-K)") (class "Default")
      (node (ref "D5") (pin "2") (pinfunction "K_2") (pintype "passive"))
      (node (ref "R78") (pin "1") (pinfunction "1_1") (pintype "passive"))
    )
    (net (code "108") (name "Net-(D6-K)") (class "Default")
      (node (ref "D6") (pin "2") (pinfunction "K_2") (pintype "passive"))
      (node (ref "R79") (pin "1") (pinfunction "1_1") (pintype "passive"))
    )
    (net (code "109") (name "unconnected-(U7A-3V3-Pad4)") (class "Default")
      (node (ref "U7") (pin "4") (pinfunction "3V3_4") (pintype "passive+no_connect"))
    )
    (net (code "110") (name "unconnected-(U7A-5V-Pad5)") (class "Default")
      (node (ref "U7") (pin "5") (pinfunction "5V_5") (pintype "passive"))
    )
    (net (code "111") (name "unconnected-(U7A-IOREF-Pad2)") (class "Default")
      (node (ref "U7") (pin "2") (pinfunction "IOREF_2") (pintype "passive+no_connect"))
    )
    (net (code "112") (name "unconnected-(U7A-NC-Pad1)") (class "Default")
      (node (ref "U7") (pin "1") (pinfunction "NC_1") (pintype "passive+no_connect"))
    )
    (net (code "113") (name "unconnected-(U7A-RESET-Pad3)") (class "Default")
      (node (ref "U7") (pin "3") (pinfunction "RESET_3") (pintype "passive"))
    )
    (net (code "114") (name "unconnected-(U7A-Vin-Pad8)") (class "Default")
      (node (ref "U7") (pin "8") (pinfunction "Vin_8") (pintype "passive+no_connect"))
    )
    (net (code "115") (name "unconnected-(U7B-ANALOG_IN_4-Pad13)") (class "Default")
      (node (ref "U7") (pin "13") (pinfunction "ANALOG_IN_4_13") (pintype "passive"))
    )
    (net (code "116") (name "unconnected-(U7B-ANALOG_IN_5-Pad14)") (class "Default")
      (node (ref "U7") (pin "14") (pinfunction "ANALOG_IN_5_14") (pintype "passive"))
    )
    (net (code "117") (name "unconnected-(U7B-ANALOG_IN_6-Pad15)") (class "Default")
      (node (ref "U7") (pin "15") (pinfunction "ANALOG_IN_6_15") (pintype "passive"))
    )
    (net (code "118") (name "unconnected-(U7B-ANALOG_IN_7-Pad16)") (class "Default")
      (node (ref "U7") (pin "16") (pinfunction "ANALOG_IN_7_16") (pintype "passive"))
    )
    (net (code "119") (name "unconnected-(U7B-ANALOG_IN_8-Pad17)") (class "Default")
      (node (ref "U7") (pin "17") (pinfunction "ANALOG_IN_8_17") (pintype "passive"))
    )
    (net (code "120") (name "unconnected-(U7B-ANALOG_IN_9-Pad18)") (class "Default")
      (node (ref "U7") (pin "18") (pinfunction "ANALOG_IN_9_18") (pintype "passive"))
    )
    (net (code "121") (name "unconnected-(U7B-ANALOG_IN_10-Pad19)") (class "Default")
      (node (ref "U7") (pin "19") (pinfunction "ANALOG_IN_10_19") (pintype "passive"))
    )
    (net (code "122") (name "unconnected-(U7B-ANALOG_IN_11-Pad20)") (class "Default")
      (node (ref "U7") (pin "20") (pinfunction "ANALOG_IN_11_20") (pintype "passive"))
    )
    (net (code "123") (name "unconnected-(U7B-ANALOG_IN_12-Pad21)") (class "Default")
      (node (ref "U7") (pin "21") (pinfunction "ANALOG_IN_12_21") (pintype "passive"))
    )
    (net (code "124") (name "unconnected-(U7C-5V-Pad25)") (class "Default")
      (node (ref "U7") (pin "25") (pinfunction "5V_25") (pintype "passive"))
    )
    (net (code "125") (name "unconnected-(U7C-5V-Pad26)") (class "Default")
      (node (ref "U7") (pin "26") (pinfunction "5V_26") (pintype "passive"))
    )
    (net (code "126") (name "unconnected-(U7C-27-Pad32)") (class "Default")
      (node (ref "U7") (pin "32") (pinfunction "27_32") (pintype "passive"))
    )
    (net (code "127") (name "unconnected-(U7C-29-Pad34)") (class "Default")
      (node (ref "U7") (pin "34") (pinfunction "29_34") (pintype "passive"))
    )
    (net (code "128") (name "unconnected-(U7C-30-Pad35)") (class "Default")
      (node (ref "U7") (pin "35") (pinfunction "30_35") (pintype "passive"))
    )
    (net (code "129") (name "unconnected-(U7C-31-Pad36)") (class "Default")
      (node (ref "U7") (pin "36") (pinfunction "31_36") (pintype "passive"))
    )
    (net (code "130") (name "unconnected-(U7C-32-Pad37)") (class "Default")
      (node (ref "U7") (pin "37") (pinfunction "32_37") (pintype "passive"))
    )
    (net (code "131") (name "unconnected-(U7C-33-Pad38)") (class "Default")
      (node (ref "U7") (pin "38") (pinfunction "33_38") (pintype "passive"))
    )
    (net (code "132") (name "unconnected-(U7C-34-Pad39)") (class "Default")
      (node (ref "U7") (pin "39") (pinfunction "34_39") (pintype "passive"))
    )
    (net (code "133") (name "unconnected-(U7C-35-Pad40)") (class "Default")
      (node (ref "U7") (pin "40") (pinfunction "35_40") (pintype "passive"))
    )
    (net (code "134") (name "unconnected-(U7C-37-Pad42)") (class "Default")
      (node (ref "U7") (pin "42") (pinfunction "37_42") (pintype "passive"))
    )
    (net (code "135") (name "unconnected-(U7C-39-Pad44)") (class "Default")
      (node (ref "U7") (pin "44") (pinfunction "39_44") (pintype "passive"))
    )
    (net (code "136") (name "unconnected-(U7C-41-Pad46)") (class "Default")
      (node (ref "U7") (pin "46") (pinfunction "41_46") (pintype "passive"))
    )
    (net (code "137") (name "unconnected-(U7C-43-Pad48)") (class "Default")
      (node (ref "U7") (pin "48") (pinfunction "43_48") (pintype "passive"))
    )
    (net (code "138") (name "unconnected-(U7C-44-Pad49)") (class "Default")
      (node (ref "U7") (pin "49") (pinfunction "44_49") (pintype "passive"))
    )
    (net (code "139") (name "unconnected-(U7C-45-Pad50)") (class "Default")
      (node (ref "U7") (pin "50") (pinfunction "45_50") (pintype "passive"))
    )
    (net (code "140") (name "unconnected-(U7C-46-Pad51)") (class "Default")
      (node (ref "U7") (pin "51") (pinfunction "46_51") (pintype "passive"))
    )
    (net (code "141") (name "unconnected-(U7C-47-Pad52)") (class "Default")
      (node (ref "U7") (pin "52") (pinfunction "47_52") (pintype "passive"))
    )
    (net (code "142") (name "unconnected-(U7C-48-Pad53)") (class "Default")
      (node (ref "U7") (pin "53") (pinfunction "48_53") (pintype "passive"))
    )
    (net (code "143") (name "unconnected-(U7C-49-Pad54)") (class "Default")
      (node (ref "U7") (pin "54") (pinfunction "49_54") (pintype "passive"))
    )
    (net (code "144") (name "unconnected-(U7D-RX-Pad69)") (class "Default")
      (node (ref "U7") (pin "69") (pinfunction "RX_69") (pintype "passive"))
    )
    (net (code "145") (name "unconnected-(U7D-RX1-Pad63)") (class "Default")
      (node (ref "U7") (pin "63") (pinfunction "RX1_63") (pintype "passive"))
    )
    (net (code "146") (name "unconnected-(U7D-RX2-Pad65)") (class "Default")
      (node (ref "U7") (pin "65") (pinfunction "RX2_65") (pintype "passive"))
    )
    (net (code "147") (name "unconnected-(U7D-RX3-Pad67)") (class "Default")
      (node (ref "U7") (pin "67") (pinfunction "RX3_67") (pintype "passive"))
    )
    (net (code "148") (name "unconnected-(U7D-SCL-Pad61)") (class "Default")
      (node (ref "U7") (pin "61") (pinfunction "SCL_61") (pintype "passive"))
    )
    (net (code "149") (name "unconnected-(U7D-SDA-Pad62)") (class "Default")
      (node (ref "U7") (pin "62") (pinfunction "SDA_62") (pintype "passive"))
    )
    (net (code "150") (name "unconnected-(U7D-TX-Pad70)") (class "Default")
      (node (ref "U7") (pin "70") (pinfunction "TX_70") (pintype "passive"))
    )
    (net (code "151") (name "unconnected-(U7D-TX1-Pad64)") (class "Default")
      (node (ref "U7") (pin "64") (pinfunction "TX1_64") (pintype "passive"))
    )
    (net (code "152") (name "unconnected-(U7D-TX2-Pad66)") (class "Default")
      (node (ref "U7") (pin "66") (pinfunction "TX2_66") (pintype "passive"))
    )
    (net (code "153") (name "unconnected-(U7D-TX3-Pad68)") (class "Default")
      (node (ref "U7") (pin "68") (pinfunction "TX3_68") (pintype "passive"))
    )
    (net (code "154") (name "unconnected-(U7E-PWM_4-Pad73)") (class "Default")
      (node (ref "U7") (pin "73") (pinfunction "PWM_4_73") (pintype "passive"))
    )
    (net (code "155") (name "unconnected-(U7E-PWM_7-Pad76)") (class "Default")
      (node (ref "U7") (pin "76") (pinfunction "PWM_7_76") (pintype "passive"))
    )
    (net (code "156") (name "unconnected-(U7F-AREF-Pad84)") (class "Default")
      (node (ref "U7") (pin "84") (pinfunction "AREF_84") (pintype "passive"))
    )
    (net (code "157") (name "unconnected-(U7G-5V-Pad88)") (class "Default")
      (node (ref "U7") (pin "88") (pinfunction "5V_88") (pintype "passive"))
    )
    (net (code "158") (name "unconnected-(U7G-GND-Pad92)") (class "Default")
      (node (ref "U7") (pin "92") (pinfunction "GND_92") (pintype "passive"))
    )
    (net (code "159") (name "unconnected-(U7G-MISO-Pad87)") (class "Default")
      (node (ref "U7") (pin "87") (pinfunction "MISO_87") (pintype "passive"))
    )
    (net (code "160") (name "unconnected-(U7G-MOSI-Pad90)") (class "Default")
      (node (ref "U7") (pin "90") (pinfunction "MOSI_90") (pintype "passive"))
    )
    (net (code "161") (name "unconnected-(U7G-RESET-Pad91)") (class "Default")
      (node (ref "U7") (pin "91") (pinfunction "RESET_91") (pintype "passive"))
    )
    (net (code "162") (name "unconnected-(U7G-SCK-Pad89)") (class "Default")
      (node (ref "U7") (pin "89") (pinfunction "SCK_89") (pintype "passive"))
    )
    (net (code "163") (name "unconnected-(U7H-5V-Pad94)") (class "Default")
      (node (ref "U7") (pin "94") (pinfunction "5V_94") (pintype "passive"))
    )
    (net (code "164") (name "unconnected-(U7H-GND-Pad98)") (class "Default")
      (node (ref "U7") (pin "98") (pinfunction "GND_98") (pintype "passive"))
    )
    (net (code "165") (name "unconnected-(U7H-MISO2-Pad93)") (class "Default")
      (node (ref "U7") (pin "93") (pinfunction "MISO2_93") (pintype "passive"))
    )
    (net (code "166") (name "unconnected-(U7H-MOSI2-Pad96)") (class "Default")
      (node (ref "U7") (pin "96") (pinfunction "MOSI2_96") (pintype "passive"))
    )
    (net (code "167") (name "unconnected-(U7H-RESET-Pad97)") (class "Default")
      (node (ref "U7") (pin "97") (pinfunction "RESET_97") (pintype "passive"))
    )
    (net (code "168") (name "unconnected-(U7H-SCK2-Pad95)") (class "Default")
      (node (ref "U7") (pin "95") (pinfunction "SCK2_95") (pintype "passive"))
    )
    (net (code "169") (name "unconnected-(U10A-3V3-Pad4)") (class "Default")
      (node (ref "U10") (pin "4") (pinfunction "3V3_4") (pintype "passive+no_connect"))
    )
    (net (code "170") (name "unconnected-(U10A-5V-Pad5)") (class "Default")
      (node (ref "U10") (pin "5") (pinfunction "5V_5") (pintype "passive"))
    )
    (net (code "171") (name "unconnected-(U10A-IOREF-Pad2)") (class "Default")
      (node (ref "U10") (pin "2") (pinfunction "IOREF_2") (pintype "passive+no_connect"))
    )
    (net (code "172") (name "unconnected-(U10A-NC-Pad1)") (class "Default")
      (node (ref "U10") (pin "1") (pinfunction "NC_1") (pintype "passive+no_connect"))
    )
    (net (code "173") (name "unconnected-(U10A-RESET-Pad3)") (class "Default")
      (node (ref "U10") (pin "3") (pinfunction "RESET_3") (pintype "passive"))
    )
    (net (code "174") (name "unconnected-(U10A-Vin-Pad8)") (class "Default")
      (node (ref "U10") (pin "8") (pinfunction "Vin_8") (pintype "passive+no_connect"))
    )
    (net (code "175") (name "unconnected-(U10B-ANALOG_IN_2-Pad11)") (class "Default")
      (node (ref "U10") (pin "11") (pinfunction "ANALOG_IN_2_11") (pintype "passive"))
    )
    (net (code "176") (name "unconnected-(U10B-ANALOG_IN_5-Pad14)") (class "Default")
      (node (ref "U10") (pin "14") (pinfunction "ANALOG_IN_5_14") (pintype "passive"))
    )
    (net (code "177") (name "unconnected-(U10B-ANALOG_IN_6-Pad15)") (class "Default")
      (node (ref "U10") (pin "15") (pinfunction "ANALOG_IN_6_15") (pintype "passive"))
    )
    (net (code "178") (name "unconnected-(U10B-ANALOG_IN_7-Pad16)") (class "Default")
      (node (ref "U10") (pin "16") (pinfunction "ANALOG_IN_7_16") (pintype "passive"))
    )
    (net (code "179") (name "unconnected-(U10B-ANALOG_IN_8-Pad17)") (class "Default")
      (node (ref "U10") (pin "17") (pinfunction "ANALOG_IN_8_17") (pintype "passive"))
    )
    (net (code "180") (name "unconnected-(U10B-ANALOG_IN_9-Pad18)") (class "Default")
      (node (ref "U10") (pin "18") (pinfunction "ANALOG_IN_9_18") (pintype "passive"))
    )
    (net (code "181") (name "unconnected-(U10B-ANALOG_IN_10-Pad19)") (class "Default")
      (node (ref "U10") (pin "19") (pinfunction "ANALOG_IN_10_19") (pintype "passive"))
    )
    (net (code "182") (name "unconnected-(U10B-ANALOG_IN_11-Pad20)") (class "Default")
      (node (ref "U10") (pin "20") (pinfunction "ANALOG_IN_11_20") (pintype "passive"))
    )
    (net (code "183") (name "unconnected-(U10B-ANALOG_IN_12-Pad21)") (class "Default")
      (node (ref "U10") (pin "21") (pinfunction "ANALOG_IN_12_21") (pintype "passive"))
    )
    (net (code "184") (name "unconnected-(U10C-5V-Pad25)") (class "Default")
      (node (ref "U10") (pin "25") (pinfunction "5V_25") (pintype "passive"))
    )
    (net (code "185") (name "unconnected-(U10C-5V-Pad26)") (class "Default")
      (node (ref "U10") (pin "26") (pinfunction "5V_26") (pintype "passive"))
    )
    (net (code "186") (name "unconnected-(U10C-29-Pad34)") (class "Default")
      (node (ref "U10") (pin "34") (pinfunction "29_34") (pintype "passive"))
    )
    (net (code "187") (name "unconnected-(U10C-31-Pad36)") (class "Default")
      (node (ref "U10") (pin "36") (pinfunction "31_36") (pintype "passive"))
    )
    (net (code "188") (name "unconnected-(U10C-33-Pad38)") (class "Default")
      (node (ref "U10") (pin "38") (pinfunction "33_38") (pintype "passive"))
    )
    (net (code "189") (name "unconnected-(U10C-34-Pad39)") (class "Default")
      (node (ref "U10") (pin "39") (pinfunction "34_39") (pintype "passive"))
    )
    (net (code "190") (name "unconnected-(U10C-35-Pad40)") (class "Default")
      (node (ref "U10") (pin "40") (pinfunction "35_40") (pintype "passive"))
    )
    (net (code "191") (name "unconnected-(U10C-36-Pad41)") (class "Default")
      (node (ref "U10") (pin "41") (pinfunction "36_41") (pintype "passive"))
    )
    (net (code "192") (name "unconnected-(U10C-38-Pad43)") (class "Default")
      (node (ref "U10") (pin "43") (pinfunction "38_43") (pintype "passive"))
    )
    (net (code "193") (name "unconnected-(U10C-40-Pad45)") (class "Default")
      (node (ref "U10") (pin "45") (pinfunction "40_45") (pintype "passive"))
    )
    (net (code "194") (name "unconnected-(U10C-41-Pad46)") (class "Default")
      (node (ref "U10") (pin "46") (pinfunction "41_46") (pintype "passive"))
    )
    (net (code "195") (name "unconnected-(U10C-42-Pad47)") (class "Default")
      (node (ref "U10") (pin "47") (pinfunction "42_47") (pintype "passive"))
    )
    (net (code "196") (name "unconnected-(U10C-43-Pad48)") (class "Default")
      (node (ref "U10") (pin "48") (pinfunction "43_48") (pintype "passive"))
    )
    (net (code "197") (name "unconnected-(U10C-44-Pad49)") (class "Default")
      (node (ref "U10") (pin "49") (pinfunction "44_49") (pintype "passive"))
    )
    (net (code "198") (name "unconnected-(U10C-45-Pad50)") (class "Default")
      (node (ref "U10") (pin "50") (pinfunction "45_50") (pintype "passive"))
    )
    (net (code "199") (name "unconnected-(U10C-46-Pad51)") (class "Default")
      (node (ref "U10") (pin "51") (pinfunction "46_51") (pintype "passive"))
    )
    (net (code "200") (name "unconnected-(U10C-47-Pad52)") (class "Default")
      (node (ref "U10") (pin "52") (pinfunction "47_52") (pintype "passive"))
    )
    (net (code "201") (name "unconnected-(U10C-48-Pad53)") (class "Default")
      (node (ref "U10") (pin "53") (pinfunction "48_53") (pintype "passive"))
    )
    (net (code "202") (name "unconnected-(U10C-49-Pad54)") (class "Default")
      (node (ref "U10") (pin "54") (pinfunction "49_54") (pintype "passive"))
    )
    (net (code "203") (name "unconnected-(U10D-RX-Pad69)") (class "Default")
      (node (ref "U10") (pin "69") (pinfunction "RX_69") (pintype "passive"))
    )
    (net (code "204") (name "unconnected-(U10D-RX2-Pad65)") (class "Default")
      (node (ref "U10") (pin "65") (pinfunction "RX2_65") (pintype "passive"))
    )
    (net (code "205") (name "unconnected-(U10D-RX3-Pad67)") (class "Default")
      (node (ref "U10") (pin "67") (pinfunction "RX3_67") (pintype "passive"))
    )
    (net (code "206") (name "unconnected-(U10D-SCL-Pad61)") (class "Default")
      (node (ref "U10") (pin "61") (pinfunction "SCL_61") (pintype "passive"))
    )
    (net (code "207") (name "unconnected-(U10D-SDA-Pad62)") (class "Default")
      (node (ref "U10") (pin "62") (pinfunction "SDA_62") (pintype "passive"))
    )
    (net (code "208") (name "unconnected-(U10D-TX-Pad70)") (class "Default")
      (node (ref "U10") (pin "70") (pinfunction "TX_70") (pintype "passive"))
    )
    (net (code "209") (name "unconnected-(U10D-TX2-Pad66)") (class "Default")
      (node (ref "U10") (pin "66") (pinfunction "TX2_66") (pintype "passive"))
    )
    (net (code "210") (name "unconnected-(U10D-TX3-Pad68)") (class "Default")
      (node (ref "U10") (pin "68") (pinfunction "TX3_68") (pintype "passive"))
    )
    (net (code "211") (name "unconnected-(U10E-PWM_2-Pad71)") (class "Default")
      (node (ref "U10") (pin "71") (pinfunction "PWM_2_71") (pintype "passive"))
    )
    (net (code "212") (name "unconnected-(U10E-PWM_3-Pad72)") (class "Default")
      (node (ref "U10") (pin "72") (pinfunction "PWM_3_72") (pintype "passive"))
    )
    (net (code "213") (name "unconnected-(U10E-PWM_4-Pad73)") (class "Default")
      (node (ref "U10") (pin "73") (pinfunction "PWM_4_73") (pintype "passive"))
    )
    (net (code "214") (name "unconnected-(U10E-PWM_5-Pad74)") (class "Default")
      (node (ref "U10") (pin "74") (pinfunction "PWM_5_74") (pintype "passive"))
    )
    (net (code "215") (name "unconnected-(U10E-PWM_6-Pad75)") (class "Default")
      (node (ref "U10") (pin "75") (pinfunction "PWM_6_75") (pintype "passive"))
    )
    (net (code "216") (name "unconnected-(U10E-PWM_7-Pad76)") (class "Default")
      (node (ref "U10") (pin "76") (pinfunction "PWM_7_76") (pintype "passive"))
    )
    (net (code "217") (name "unconnected-(U10E-PWM_9-Pad78)") (class "Default")
      (node (ref "U10") (pin "78") (pinfunction "PWM_9_78") (pintype "passive"))
    )
    (net (code "218") (name "unconnected-(U10E-PWM_10-Pad79)") (class "Default")
      (node (ref "U10") (pin "79") (pinfunction "PWM_10_79") (pintype "passive"))
    )
    (net (code "219") (name "unconnected-(U10E-PWM_11-Pad80)") (class "Default")
      (node (ref "U10") (pin "80") (pinfunction "PWM_11_80") (pintype "passive"))
    )
    (net (code "220") (name "unconnected-(U10E-PWM_12-Pad81)") (class "Default")
      (node (ref "U10") (pin "81") (pinfunction "PWM_12_81") (pintype "passive"))
    )
    (net (code "221") (name "unconnected-(U10E-PWM_13-Pad82)") (class "Default")
      (node (ref "U10") (pin "82") (pinfunction "PWM_13_82") (pintype "passive"))
    )
    (net (code "222") (name "unconnected-(U10F-AREF-Pad84)") (class "Default")
      (node (ref "U10") (pin "84") (pinfunction "AREF_84") (pintype "passive"))
    )
    (net (code "223") (name "unconnected-(U10F-SCL-Pad86)") (class "Default")
      (node (ref "U10") (pin "86") (pinfunction "SCL_86") (pintype "passive"))
    )
    (net (code "224") (name "unconnected-(U10F-SDA-Pad85)") (class "Default")
      (node (ref "U10") (pin "85") (pinfunction "SDA_85") (pintype "passive"))
    )
    (net (code "225") (name "unconnected-(U10G-5V-Pad88)") (class "Default")
      (node (ref "U10") (pin "88") (pinfunction "5V_88") (pintype "passive"))
    )
    (net (code "226") (name "unconnected-(U10G-GND-Pad92)") (class "Default")
      (node (ref "U10") (pin "92") (pinfunction "GND_92") (pintype "passive"))
    )
    (net (code "227") (name "unconnected-(U10G-MISO-Pad87)") (class "Default")
      (node (ref "U10") (pin "87") (pinfunction "MISO_87") (pintype "passive"))
    )
    (net (code "228") (name "unconnected-(U10G-MOSI-Pad90)") (class "Default")
      (node (ref "U10") (pin "90") (pinfunction "MOSI_90") (pintype "passive"))
    )
    (net (code "229") (name "unconnected-(U10G-RESET-Pad91)") (class "Default")
      (node (ref "U10") (pin "91") (pinfunction "RESET_91") (pintype "passive"))
    )
    (net (code "230") (name "unconnected-(U10G-SCK-Pad89)") (class "Default")
      (node (ref "U10") (pin "89") (pinfunction "SCK_89") (pintype "passive"))
    )
    (net (code "231") (name "unconnected-(U10H-5V-Pad94)") (class "Default")
      (node (ref "U10") (pin "94") (pinfunction "5V_94") (pintype "passive"))
    )
    (net (code "232") (name "unconnected-(U10H-GND-Pad98)") (class "Default")
      (node (ref "U10") (pin "98") (pinfunction "GND_98") (pintype "passive"))
    )
    (net (code "233") (name "unconnected-(U10H-MISO2-Pad93)") (class "Default")
      (node (ref "U10") (pin "93") (pinfunction "MISO2_93") (pintype "passive"))
    )
    (net (code "234") (name "unconnected-(U10H-MOSI2-Pad96)") (class "Default")
      (node (ref "U10") (pin "96") (pinfunction "MOSI2_96") (pintype "passive"))
    )
    (net (code "235") (name "unconnected-(U10H-RESET-Pad97)") (class "Default")
      (node (ref "U10") (pin "97") (pinfunction "RESET_97") (pintype "passive"))
    )
    (net (code "236") (name "unconnected-(U10H-SCK2-Pad95)") (class "Default")
      (node (ref "U10") (pin "95") (pinfunction "SCK2_95") (pintype "passive"))
    )
    (net (code "237") (name "unconnected-(U12A-3V3-Pad4)") (class "Default")
      (node (ref "U12") (pin "4") (pinfunction "3V3_4") (pintype "passive+no_connect"))
    )
    (net (code "238") (name "unconnected-(U12A-5V-Pad5)") (class "Default")
      (node (ref "U12") (pin "5") (pinfunction "5V_5") (pintype "passive"))
    )
    (net (code "239") (name "unconnected-(U12A-IOREF-Pad2)") (class "Default")
      (node (ref "U12") (pin "2") (pinfunction "IOREF_2") (pintype "passive+no_connect"))
    )
    (net (code "240") (name "unconnected-(U12A-NC-Pad1)") (class "Default")
      (node (ref "U12") (pin "1") (pinfunction "NC_1") (pintype "passive+no_connect"))
    )
    (net (code "241") (name "unconnected-(U12A-RESET-Pad3)") (class "Default")
      (node (ref "U12") (pin "3") (pinfunction "RESET_3") (pintype "passive"))
    )
    (net (code "242") (name "unconnected-(U12A-Vin-Pad8)") (class "Default")
      (node (ref "U12") (pin "8") (pinfunction "Vin_8") (pintype "passive+no_connect"))
    )
    (net (code "243") (name "unconnected-(U12B-ANALOG_IN_12-Pad21)") (class "Default")
      (node (ref "U12") (pin "21") (pinfunction "ANALOG_IN_12_21") (pintype "passive"))
    )
    (net (code "244") (name "unconnected-(U12C-5V-Pad25)") (class "Default")
      (node (ref "U12") (pin "25") (pinfunction "5V_25") (pintype "passive"))
    )
    (net (code "245") (name "unconnected-(U12C-5V-Pad26)") (class "Default")
      (node (ref "U12") (pin "26") (pinfunction "5V_26") (pintype "passive"))
    )
    (net (code "246") (name "unconnected-(U12D-RX-Pad69)") (class "Default")
      (node (ref "U12") (pin "69") (pinfunction "RX_69") (pintype "passive"))
    )
    (net (code "247") (name "unconnected-(U12D-RX1-Pad63)") (class "Default")
      (node (ref "U12") (pin "63") (pinfunction "RX1_63") (pintype "passive"))
    )
    (net (code "248") (name "unconnected-(U12D-RX2-Pad65)") (class "Default")
      (node (ref "U12") (pin "65") (pinfunction "RX2_65") (pintype "passive"))
    )
    (net (code "249") (name "unconnected-(U12D-RX3-Pad67)") (class "Default")
      (node (ref "U12") (pin "67") (pinfunction "RX3_67") (pintype "passive"))
    )
    (net (code "250") (name "unconnected-(U12D-SCL-Pad61)") (class "Default")
      (node (ref "U12") (pin "61") (pinfunction "SCL_61") (pintype "passive"))
    )
    (net (code "251") (name "unconnected-(U12D-SDA-Pad62)") (class "Default")
      (node (ref "U12") (pin "62") (pinfunction "SDA_62") (pintype "passive"))
    )
    (net (code "252") (name "unconnected-(U12D-TX-Pad70)") (class "Default")
      (node (ref "U12") (pin "70") (pinfunction "TX_70") (pintype "passive"))
    )
    (net (code "253") (name "unconnected-(U12D-TX1-Pad64)") (class "Default")
      (node (ref "U12") (pin "64") (pinfunction "TX1_64") (pintype "passive"))
    )
    (net (code "254") (name "unconnected-(U12D-TX2-Pad66)") (class "Default")
      (node (ref "U12") (pin "66") (pinfunction "TX2_66") (pintype "passive"))
    )
    (net (code "255") (name "unconnected-(U12D-TX3-Pad68)") (class "Default")
      (node (ref "U12") (pin "68") (pinfunction "TX3_68") (pintype "passive"))
    )
    (net (code "256") (name "unconnected-(U12E-PWM_2-Pad71)") (class "Default")
      (node (ref "U12") (pin "71") (pinfunction "PWM_2_71") (pintype "passive"))
    )
    (net (code "257") (name "unconnected-(U12E-PWM_3-Pad72)") (class "Default")
      (node (ref "U12") (pin "72") (pinfunction "PWM_3_72") (pintype "passive"))
    )
    (net (code "258") (name "unconnected-(U12E-PWM_4-Pad73)") (class "Default")
      (node (ref "U12") (pin "73") (pinfunction "PWM_4_73") (pintype "passive"))
    )
    (net (code "259") (name "unconnected-(U12E-PWM_5-Pad74)") (class "Default")
      (node (ref "U12") (pin "74") (pinfunction "PWM_5_74") (pintype "passive"))
    )
    (net (code "260") (name "unconnected-(U12E-PWM_6-Pad75)") (class "Default")
      (node (ref "U12") (pin "75") (pinfunction "PWM_6_75") (pintype "passive"))
    )
    (net (code "261") (name "unconnected-(U12E-PWM_7-Pad76)") (class "Default")
      (node (ref "U12") (pin "76") (pinfunction "PWM_7_76") (pintype "passive"))
    )
    (net (code "262") (name "unconnected-(U12E-PWM_9-Pad78)") (class "Default")
      (node (ref "U12") (pin "78") (pinfunction "PWM_9_78") (pintype "passive"))
    )
    (net (code "263") (name "unconnected-(U12E-PWM_10-Pad79)") (class "Default")
      (node (ref "U12") (pin "79") (pinfunction "PWM_10_79") (pintype "passive"))
    )
    (net (code "264") (name "unconnected-(U12E-PWM_11-Pad80)") (class "Default")
      (node (ref "U12") (pin "80") (pinfunction "PWM_11_80") (pintype "passive"))
    )
    (net (code "265") (name "unconnected-(U12E-PWM_12-Pad81)") (class "Default")
      (node (ref "U12") (pin "81") (pinfunction "PWM_12_81") (pintype "passive"))
    )
    (net (code "266") (name "unconnected-(U12E-PWM_13-Pad82)") (class "Default")
      (node (ref "U12") (pin "82") (pinfunction "PWM_13_82") (pintype "passive"))
    )
    (net (code "267") (name "unconnected-(U12F-AREF-Pad84)") (class "Default")
      (node (ref "U12") (pin "84") (pinfunction "AREF_84") (pintype "passive"))
    )
    (net (code "268") (name "unconnected-(U12G-5V-Pad88)") (class "Default")
      (node (ref "U12") (pin "88") (pinfunction "5V_88") (pintype "passive"))
    )
    (net (code "269") (name "unconnected-(U12G-GND-Pad92)") (class "Default")
      (node (ref "U12") (pin "92") (pinfunction "GND_92") (pintype "passive"))
    )
    (net (code "270") (name "unconnected-(U12G-MISO-Pad87)") (class "Default")
      (node (ref "U12") (pin "87") (pinfunction "MISO_87") (pintype "passive"))
    )
    (net (code "271") (name "unconnected-(U12G-MOSI-Pad90)") (class "Default")
      (node (ref "U12") (pin "90") (pinfunction "MOSI_90") (pintype "passive"))
    )
    (net (code "272") (name "unconnected-(U12G-RESET-Pad91)") (class "Default")
      (node (ref "U12") (pin "91") (pinfunction "RESET_91") (pintype "passive"))
    )
    (net (code "273") (name "unconnected-(U12G-SCK-Pad89)") (class "Default")
      (node (ref "U12") (pin "89") (pinfunction "SCK_89") (pintype "passive"))
    )
    (net (code "274") (name "unconnected-(U12H-5V-Pad94)") (class "Default")
      (node (ref "U12") (pin "94") (pinfunction "5V_94") (pintype "passive"))
    )
    (net (code "275") (name "unconnected-(U12H-GND-Pad98)") (class "Default")
      (node (ref "U12") (pin "98") (pinfunction "GND_98") (pintype "passive"))
    )
    (net (code "276") (name "unconnected-(U12H-MISO2-Pad93)") (class "Default")
      (node (ref "U12") (pin "93") (pinfunction "MISO2_93") (pintype "passive"))
    )
    (net (code "277") (name "unconnected-(U12H-MOSI2-Pad96)") (class "Default")
      (node (ref "U12") (pin "96") (pinfunction "MOSI2_96") (pintype "passive"))
    )
    (net (code "278") (name "unconnected-(U12H-RESET-Pad97)") (class "Default")
      (node (ref "U12") (pin "97") (pinfunction "RESET_97") (pintype "passive"))
    )
    (net (code "279") (name "unconnected-(U12H-SCK2-Pad95)") (class "Default")
      (node (ref "U12") (pin "95") (pinfunction "SCK2_95") (pintype "passive"))
    )
  )
)
